# Power.net
KiCad netlist of a schematic drawn in Altium Designer
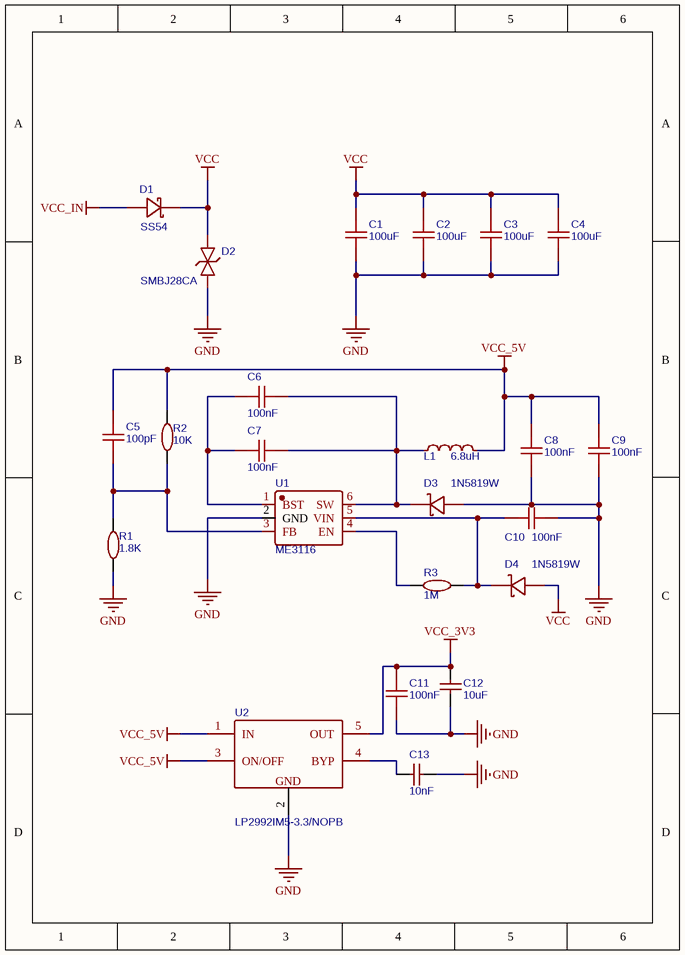
[diagram p0: Power.SchDoc]

(export (version "E")
  (design (tool "Eeschema 10.0.6"))
  (components
    (comp (ref "C1")
      (value "100uF")
      (footprint "C1206")
      (fields
        (field (name "BOM_SUPPLIER PART") "C312983")
        (field (name "BOM_MANUFACTURER PART") "GRM31CR61A107ME05L")
        (field (name "CONTRIBUTOR") "LCSC")
      )
      (libsource (lib "100uF") (part "100uF"))
    )
    (comp (ref "C2")
      (value "100uF")
      (footprint "C1206")
      (fields
        (field (name "BOM_SUPPLIER PART") "C312983")
        (field (name "BOM_MANUFACTURER PART") "GRM31CR61A107ME05L")
        (field (name "CONTRIBUTOR") "LCSC")
      )
      (libsource (lib "100uF") (part "100uF"))
    )
    (comp (ref "C3")
      (value "100uF")
      (footprint "C1206")
      (fields
        (field (name "BOM_SUPPLIER PART") "C312983")
        (field (name "BOM_MANUFACTURER PART") "GRM31CR61A107ME05L")
        (field (name "CONTRIBUTOR") "LCSC")
      )
      (libsource (lib "100uF") (part "100uF"))
    )
    (comp (ref "C4")
      (value "100uF")
      (footprint "C1206")
      (fields
        (field (name "BOM_SUPPLIER PART") "C312983")
        (field (name "BOM_MANUFACTURER PART") "GRM31CR61A107ME05L")
        (field (name "CONTRIBUTOR") "LCSC")
      )
      (libsource (lib "100uF") (part "100uF"))
    )
    (comp (ref "C5")
      (value "100pF")
      (footprint "C0603")
      (fields
        (field (name "BOM_MANUFACTURER PART") "CC0603JRNPO9BN101")
        (field (name "BOM_SUPPLIER PART") "C14665")
      )
      (libsource (lib "100pF") (part "100pF"))
    )
    (comp (ref "C6")
      (value "100nF")
      (footprint "C0603")
      (fields
        (field (name "BOM_MANUFACTURER PART") "CL10B104KB8NNNC")
        (field (name "BOM_SUPPLIER PART") "C1591")
      )
      (libsource (lib "0.1uF") (part "100nF"))
    )
    (comp (ref "C7")
      (value "100nF")
      (footprint "C0603")
      (fields
        (field (name "BOM_MANUFACTURER PART") "CL10B104KB8NNNC")
        (field (name "BOM_SUPPLIER PART") "C1591")
      )
      (libsource (lib "0.1uF") (part "100nF"))
    )
    (comp (ref "C8")
      (value "100nF")
      (footprint "C0603")
      (fields
        (field (name "BOM_MANUFACTURER PART") "CL10B104KB8NNNC")
        (field (name "BOM_SUPPLIER PART") "C1591")
      )
      (libsource (lib "0.1uF") (part "100nF"))
    )
    (comp (ref "C9")
      (value "100nF")
      (footprint "C0603")
      (fields
        (field (name "BOM_MANUFACTURER PART") "CL10B104KB8NNNC")
        (field (name "BOM_SUPPLIER PART") "C1591")
      )
      (libsource (lib "0.1uF") (part "100nF"))
    )
    (comp (ref "C10")
      (value "100nF")
      (footprint "C0603")
      (fields
        (field (name "BOM_MANUFACTURER PART") "CL10B104KB8NNNC")
        (field (name "BOM_SUPPLIER PART") "C1591")
      )
      (libsource (lib "0.1uF") (part "100nF"))
    )
    (comp (ref "C11")
      (value "100nF")
      (footprint "C0603")
      (fields
        (field (name "BOM_MANUFACTURER PART") "CL10B104KB8NNNC")
        (field (name "BOM_SUPPLIER PART") "C1591")
      )
      (libsource (lib "0.1uF") (part "100nF"))
    )
    (comp (ref "C12")
      (value "10uF")
      (footprint "C1206")
      (fields
        (field (name "BOM_MANUFACTURER PART") "CL31A106KBHNNNE")
        (field (name "BOM_SUPPLIER PART") "C13585")
      )
      (libsource (lib "10uF") (part "10uF"))
    )
    (comp (ref "C13")
      (value "10nF")
      (footprint "C0603")
      (fields
        (field (name "BOM_MANUFACTURER PART") "CC0603KRX7R9BB103")
        (field (name "BOM_SUPPLIER PART") "C100042")
      )
      (libsource (lib "10nF") (part "10nF"))
    )
    (comp (ref "D1")
      (value "SS54")
      (footprint "SMA_L4.3-W2.6-LS5.0-RD")
      (fields (field (name "BOM_SUPPLIER PART") "C727065") (field (name "CONTRIBUTOR") "LCSC"))
      (libsource (lib "SS54") (part "SS54_C727065"))
    )
    (comp (ref "D2")
      (value "SMBJ28CA")
      (footprint "SMB_L4.6-W3.6-LS5.3-BI")
      (fields (field (name "BOM_SUPPLIER PART") "C908204") (field (name "CONTRIBUTOR") "LCSC"))
      (libsource (lib "SMBJ28CA") (part "SMBJ28CA_C908204"))
    )
    (comp (ref "D3")
      (value "1N5819W")
      (footprint "SOD-123F_L2.8-W1.8-LS3.7-RD")
      (fields (field (name "BOM_SUPPLIER PART") "C169540") (field (name "CONTRIBUTOR") "LCSC"))
      (libsource (lib "5819") (part "1N5819W"))
    )
    (comp (ref "D4")
      (value "1N5819W")
      (footprint "SOD-123F_L2.8-W1.8-LS3.7-RD")
      (fields (field (name "BOM_SUPPLIER PART") "C169540") (field (name "CONTRIBUTOR") "LCSC"))
      (libsource (lib "5819") (part "1N5819W"))
    )
    (comp (ref "L1")
      (value "6.8uH")
      (footprint "IND-SMD_L7.0-W6.6")
      (fields
        (field (name "BOM_SUPPLIER PART") "C408449")
        (field (name "BOM_MANUFACTURER PART") "MWSA0603S-6R8MT")
        (field (name "CONTRIBUTOR") "LCSC")
      )
      (libsource (lib "6.8uH") (part "6.8uH"))
    )
    (comp (ref "R1")
      (value "1.8K")
      (footprint "R0603")
      (fields
        (field (name "BOM_MANUFACTURER PART") "0603WAF1801T5E")
        (field (name "BOM_SUPPLIER PART") "C4177")
      )
      (libsource (lib "1.8K") (part "1.8K"))
    )
    (comp (ref "R2")
      (value "10K")
      (footprint "R0603")
      (fields
        (field (name "BOM_MANUFACTURER PART") "0603WAF1002T5E")
        (field (name "BOM_SUPPLIER PART") "C25804")
      )
      (libsource (lib "10K") (part "10K"))
    )
    (comp (ref "R3")
      (value "1M")
      (footprint "R0603")
      (fields
        (field (name "BOM_MANUFACTURER PART") "0603WAF1004T5E")
        (field (name "BOM_SUPPLIER PART") "C22935")
      )
      (libsource (lib "1M") (part "1M"))
    )
    (comp (ref "U1")
      (value "ME3116")
      (footprint "SOT-23-6_L2.9-W1.6-P0.95-LS2.8-BL")
      (fields
        (field (name "BOM_SUPPLIER PART") "C2844924")
        (field (name "BOM_MANUFACTURER PART") "TP6841S6-A")
        (field (name "CONTRIBUTOR") "LCSC")
      )
      (libsource (lib "ME3116") (part "TP6841S6-A"))
    )
    (comp (ref "U2")
      (value "LP2992IM5-3.3/NOPB")
      (footprint "SOT-23-5_L3.0-W1.7-P0.95-LS2.8-BR")
      (fields (field (name "BOM_SUPPLIER PART") "C129353") (field (name "CONTRIBUTOR") "LCSC"))
      (libsource (lib "LP2992IM5-3.3V") (part "LP2992IM5-3.3/NOPB"))
    )
  )
  (nets
    (net (code "1") (name "GND") (class "Default")
      (node (ref "C1") (pin "2") (pinfunction "2_2") (pintype "passive"))
      (node (ref "C10") (pin "1") (pinfunction "1_1") (pintype "passive"))
      (node (ref "C11") (pin "1") (pinfunction "1_1") (pintype "passive"))
      (node (ref "C12") (pin "1") (pinfunction "1_1") (pintype "passive"))
      (node (ref "C13") (pin "2") (pinfunction "2_2") (pintype "passive"))
      (node (ref "C2") (pin "2") (pinfunction "2_2") (pintype "passive"))
      (node (ref "C3") (pin "2") (pinfunction "2_2") (pintype "passive"))
      (node (ref "C4") (pin "2") (pinfunction "2_2") (pintype "passive"))
      (node (ref "C8") (pin "1") (pinfunction "1_1") (pintype "passive"))
      (node (ref "C9") (pin "1") (pinfunction "1_1") (pintype "passive"))
      (node (ref "D2") (pin "1") (pinfunction "1_1") (pintype "passive"))
      (node (ref "D3") (pin "2") (pinfunction "2_2") (pintype "passive"))
      (node (ref "R1") (pin "1") (pinfunction "1_1") (pintype "passive"))
      (node (ref "U1") (pin "2") (pinfunction "GND_2") (pintype "passive"))
      (node (ref "U2") (pin "2") (pinfunction "GND_2") (pintype "passive"))
    )
    (net (code "2") (name "Net-(U1-BST)") (class "Default")
      (node (ref "C6") (pin "1") (pinfunction "1_1") (pintype "passive"))
      (node (ref "C7") (pin "1") (pinfunction "1_1") (pintype "passive"))
      (node (ref "U1") (pin "1") (pinfunction "BST_1") (pintype "passive"))
    )
    (net (code "3") (name "Net-(U1-EN)") (class "Default")
      (node (ref "R3") (pin "1") (pinfunction "1_1") (pintype "passive"))
      (node (ref "U1") (pin "4") (pinfunction "EN_4") (pintype "passive"))
    )
    (net (code "4") (name "Net-(U1-FB)") (class "Default")
      (node (ref "C5") (pin "1") (pinfunction "1_1") (pintype "passive"))
      (node (ref "R1") (pin "2") (pinfunction "2_2") (pintype "passive"))
      (node (ref "R2") (pin "1") (pinfunction "1_1") (pintype "passive"))
      (node (ref "U1") (pin "3") (pinfunction "FB_3") (pintype "passive"))
    )
    (net (code "5") (name "Net-(U1-SW)") (class "Default")
      (node (ref "C6") (pin "2") (pinfunction "2_2") (pintype "passive"))
      (node (ref "C7") (pin "2") (pinfunction "2_2") (pintype "passive"))
      (node (ref "D3") (pin "1") (pinfunction "1_1") (pintype "passive"))
      (node (ref "L1") (pin "1") (pinfunction "1_1") (pintype "passive"))
      (node (ref "U1") (pin "6") (pinfunction "SW_6") (pintype "passive"))
    )
    (net (code "6") (name "Net-(U1-VIN)") (class "Default")
      (node (ref "C10") (pin "2") (pinfunction "2_2") (pintype "passive"))
      (node (ref "D4") (pin "1") (pinfunction "1_1") (pintype "passive"))
      (node (ref "R3") (pin "2") (pinfunction "2_2") (pintype "passive"))
      (node (ref "U1") (pin "5") (pinfunction "VIN_5") (pintype "passive"))
    )
    (net (code "7") (name "Net-(U2-BYP)") (class "Default")
      (node (ref "C13") (pin "1") (pinfunction "1_1") (pintype "passive"))
      (node (ref "U2") (pin "4") (pinfunction "BYP_4") (pintype "passive"))
    )
    (net (code "8") (name "VCC") (class "Default")
      (node (ref "C1") (pin "1") (pinfunction "1_1") (pintype "passive"))
      (node (ref "C2") (pin "1") (pinfunction "1_1") (pintype "passive"))
      (node (ref "C3") (pin "1") (pinfunction "1_1") (pintype "passive"))
      (node (ref "C4") (pin "1") (pinfunction "1_1") (pintype "passive"))
      (node (ref "D1") (pin "1") (pinfunction "1_1") (pintype "passive"))
      (node (ref "D2") (pin "2") (pinfunction "2_2") (pintype "passive"))
      (node (ref "D4") (pin "2") (pinfunction "2_2") (pintype "passive"))
    )
    (net (code "9") (name "VCC_3V3") (class "Default")
      (node (ref "C11") (pin "2") (pinfunction "2_2") (pintype "passive"))
      (node (ref "C12") (pin "2") (pinfunction "2_2") (pintype "passive"))
      (node (ref "U2") (pin "5") (pinfunction "OUT_5") (pintype "passive"))
    )
    (net (code "10") (name "VCC_5V") (class "Default")
      (node (ref "C5") (pin "2") (pinfunction "2_2") (pintype "passive"))
      (node (ref "C8") (pin "2") (pinfunction "2_2") (pintype "passive"))
      (node (ref "C9") (pin "2") (pinfunction "2_2") (pintype "passive"))
      (node (ref "L1") (pin "2") (pinfunction "2_2") (pintype "passive"))
      (node (ref "R2") (pin "2") (pinfunction "2_2") (pintype "passive"))
      (node (ref "U2") (pin "1") (pinfunction "IN_1") (pintype "passive"))
      (node (ref "U2") (pin "3") (pinfunction "ON/OFF_3") (pintype "passive"))
    )
    (net (code "11") (name "VCC_IN") (class "Default")
      (node (ref "D1") (pin "2") (pinfunction "2_2") (pintype "passive"))
    )
  )
)
